# RC_Receiver.net
KiCad netlist of a schematic drawn in EAGLE
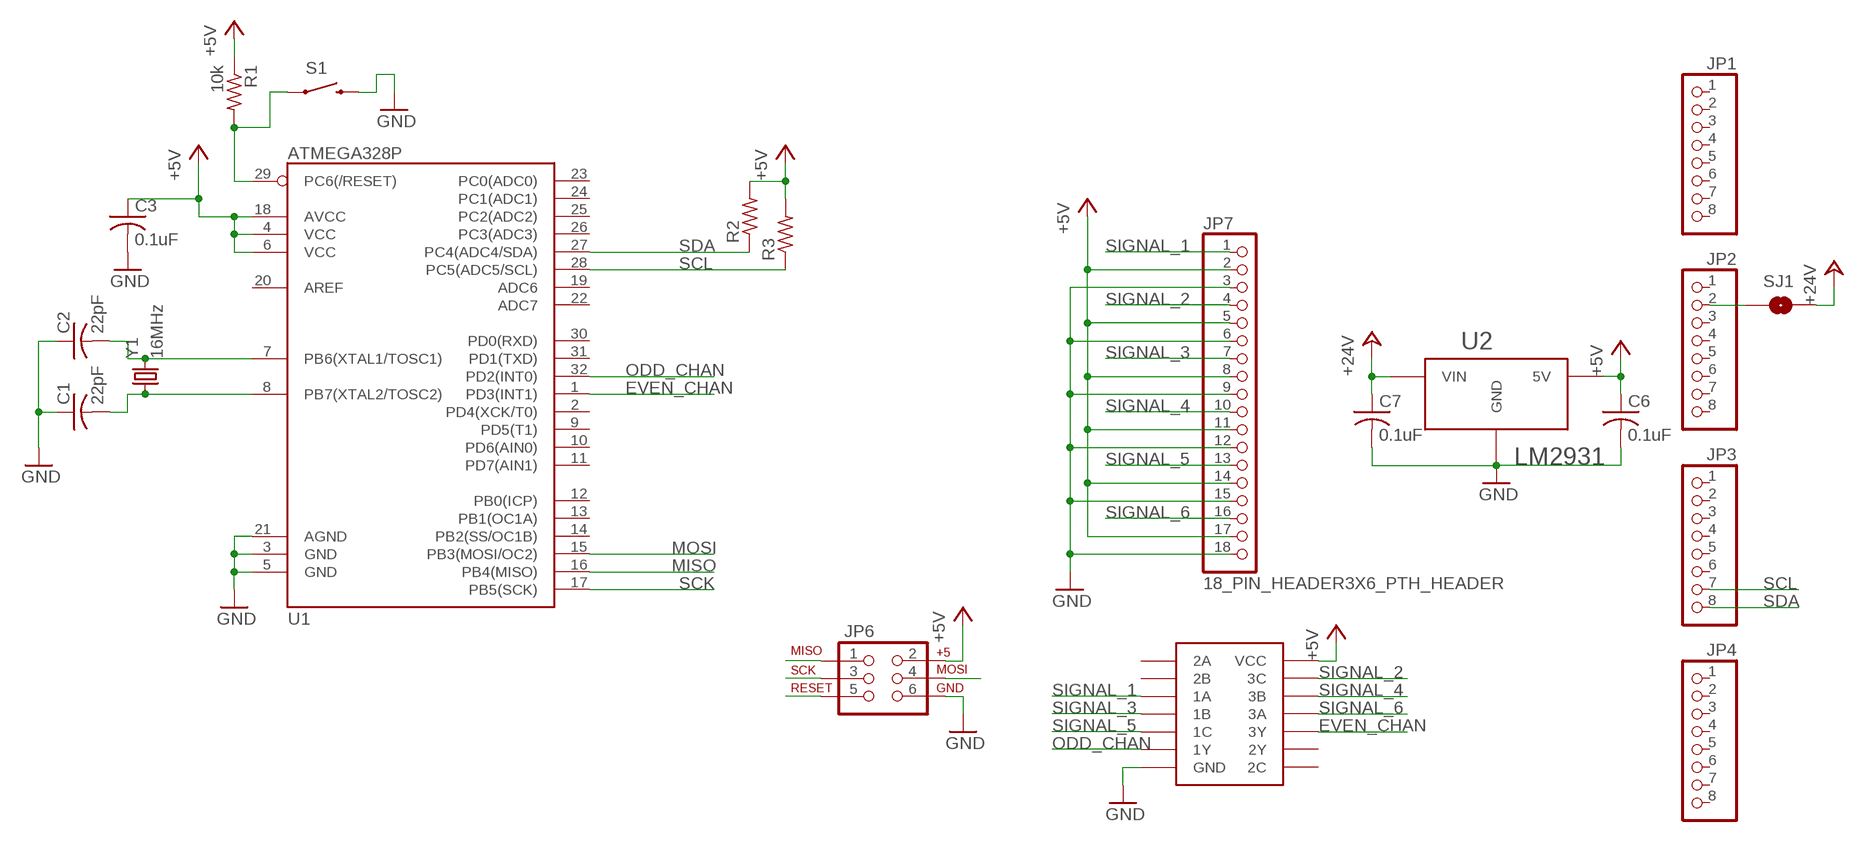
[diagram p0: schematic, sheet 1]

(export (version "E")
  (design (tool "Eeschema 10.0.6"))
  (components
    (comp (ref "C1")
      (value "22pF")
      (footprint "eagle-import:C0603")
      (libsource (lib "eagle-import") (part "C-USC0603"))
    )
    (comp (ref "C2")
      (value "22pF")
      (footprint "eagle-import:C0603")
      (libsource (lib "eagle-import") (part "C-USC0603"))
    )
    (comp (ref "C3")
      (value "0.1uF")
      (footprint "eagle-import:C0603")
      (libsource (lib "eagle-import") (part "C-USC0603"))
    )
    (comp (ref "C6")
      (value "0.1uF")
      (footprint "eagle-import:C0603")
      (libsource (lib "eagle-import") (part "C-USC0603"))
    )
    (comp (ref "C7")
      (value "0.1uF")
      (footprint "eagle-import:C0603")
      (libsource (lib "eagle-import") (part "C-USC0603"))
    )
    (comp (ref "JP1")
      (value "PINHD-1X81X08_NO_SILK")
      (footprint "eagle-import:1X08_NO_SS")
      (libsource (lib "eagle-import") (part "PINHD-1X81X08_NO_SILK"))
    )
    (comp (ref "JP2")
      (value "PINHD-1X81X08_NO_SILK")
      (footprint "eagle-import:1X08_NO_SS")
      (libsource (lib "eagle-import") (part "PINHD-1X81X08_NO_SILK"))
    )
    (comp (ref "JP3")
      (value "PINHD-1X81X08_NO_SILK")
      (footprint "eagle-import:1X08_NO_SS")
      (libsource (lib "eagle-import") (part "PINHD-1X81X08_NO_SILK"))
    )
    (comp (ref "JP4")
      (value "PINHD-1X81X08_NO_SILK")
      (footprint "eagle-import:1X08_NO_SS")
      (libsource (lib "eagle-import") (part "PINHD-1X81X08_NO_SILK"))
    )
    (comp (ref "JP6")
      (value "AVR_SPI_PRG_62X3_LOCK")
      (footprint "eagle-import:2X3_LOCK")
      (libsource (lib "eagle-import") (part "AVR_SPI_PRG_62X3_LOCK"))
    )
    (comp (ref "JP7")
      (value "18_PIN_HEADER3X6_PTH_HEADER")
      (footprint "eagle-import:3X6_PTH_HEADER")
      (libsource (lib "eagle-import") (part "18_PIN_HEADER3X6_PTH_HEADER"))
    )
    (comp (ref "R1")
      (value "10k")
      (footprint "eagle-import:R0603")
      (libsource (lib "eagle-import") (part "R-US_R0603"))
    )
    (comp (ref "R2")
      (value "R-US_R0603")
      (footprint "eagle-import:R0603")
      (libsource (lib "eagle-import") (part "R-US_R0603"))
    )
    (comp (ref "R3")
      (value "R-US_R0603")
      (footprint "eagle-import:R0603")
      (libsource (lib "eagle-import") (part "R-US_R0603"))
    )
    (comp (ref "S1")
      (value "SWITCH-MOMENTARY-2SMD")
      (footprint "eagle-import:TACTILE_SWITCH_SMD")
      (libsource (lib "eagle-import") (part "SWITCH-MOMENTARY-2SMD"))
    )
    (comp (ref "SJ1")
      (value "SOLDERJUMPERNC")
      (footprint "eagle-import:SJ_2S")
      (libsource (lib "eagle-import") (part "SOLDERJUMPERNC"))
    )
    (comp (ref "U$1")
      (value "C74HC407514-SOIC")
      (footprint "eagle-import:14-SOIC")
      (fields (field (name "PART#") "296-14534-1-ND"))
      (libsource (lib "eagle-import") (part "C74HC407514-SOIC"))
    )
    (comp (ref "U1")
      (value "ATMEGA328P")
      (footprint "eagle-import:TQFP32-08")
      (libsource (lib "eagle-import") (part "ATMEGA328_SMT"))
    )
    (comp (ref "U2")
      (value "LM2931")
      (footprint "eagle-import:TO263")
      (fields (field (name "PART#") "lm2931"))
      (libsource (lib "eagle-import") (part "LM2931"))
    )
    (comp (ref "Y1")
      (value "16MHz")
      (footprint "eagle-import:CRYSTAL-SMD-5X3")
      (fields (field (name "PART#") "535-10226-1-ND"))
      (libsource (lib "eagle-import") (part "CRYSTAL5X3"))
    )
  )
  (nets
    (net (code "1") (name "+5V") (class "Default")
      (node (ref "C3") (pin "1") (pinfunction "1_1") (pintype "passive"))
      (node (ref "C6") (pin "1") (pinfunction "1_1") (pintype "passive"))
      (node (ref "JP6") (pin "2") (pinfunction "2_2") (pintype "passive"))
      (node (ref "JP7") (pin "11") (pinfunction "11_11") (pintype "passive"))
      (node (ref "JP7") (pin "14") (pinfunction "14_14") (pintype "passive"))
      (node (ref "JP7") (pin "17") (pinfunction "17_17") (pintype "passive"))
      (node (ref "JP7") (pin "2") (pinfunction "2_2") (pintype "passive"))
      (node (ref "JP7") (pin "5") (pinfunction "5_5") (pintype "passive"))
      (node (ref "JP7") (pin "8") (pinfunction "8_8") (pintype "passive"))
      (node (ref "R1") (pin "1") (pinfunction "1_1") (pintype "passive"))
      (node (ref "R2") (pin "2") (pinfunction "2_2") (pintype "passive"))
      (node (ref "R3") (pin "2") (pinfunction "2_2") (pintype "passive"))
      (node (ref "U$1") (pin "P$14") (pinfunction "VCC_P$14") (pintype "power_in"))
      (node (ref "U1") (pin "18") (pinfunction "AVCC_18") (pintype "bidirectional"))
      (node (ref "U1") (pin "4") (pinfunction "VCC_4") (pintype "bidirectional"))
      (node (ref "U1") (pin "6") (pinfunction "VCC_6") (pintype "bidirectional"))
      (node (ref "U2") (pin "P$3") (pinfunction "5V_P$3") (pintype "bidirectional"))
    )
    (net (code "2") (name "+24V") (class "Default")
      (node (ref "C7") (pin "1") (pinfunction "1_1") (pintype "passive"))
      (node (ref "SJ1") (pin "2") (pinfunction "2_2") (pintype "passive"))
      (node (ref "U2") (pin "P$2") (pinfunction "VIN_P$2") (pintype "bidirectional"))
    )
    (net (code "3") (name "/EVEN_CHAN") (class "Default")
      (node (ref "U$1") (pin "P$12") (pinfunction "3Y_P$12") (pintype "bidirectional"))
      (node (ref "U1") (pin "1") (pinfunction "PD3(INT1)_1") (pintype "bidirectional"))
    )
    (net (code "4") (name "/MISO") (class "Default")
      (node (ref "JP6") (pin "1") (pinfunction "1_1") (pintype "passive"))
      (node (ref "U1") (pin "16") (pinfunction "PB4(MISO)_16") (pintype "bidirectional"))
    )
    (net (code "5") (name "/MOSI") (class "Default")
      (node (ref "JP6") (pin "4") (pinfunction "4_4") (pintype "passive"))
      (node (ref "U1") (pin "15") (pinfunction "PB3(MOSI/OC2)_15") (pintype "bidirectional"))
    )
    (net (code "6") (name "/ODD_CHAN") (class "Default")
      (node (ref "U$1") (pin "P$4") (pinfunction "1Y_P$4") (pintype "bidirectional"))
      (node (ref "U1") (pin "32") (pinfunction "PD2(INT0)_32") (pintype "bidirectional"))
    )
    (net (code "7") (name "/RESET") (class "Default")
      (node (ref "JP6") (pin "5") (pinfunction "5_5") (pintype "passive"))
      (node (ref "R1") (pin "2") (pinfunction "2_2") (pintype "passive"))
      (node (ref "S1") (pin "1") (pinfunction "1_1") (pintype "passive"))
      (node (ref "U1") (pin "29") (pinfunction "PC6(/RESET)_29") (pintype "bidirectional"))
    )
    (net (code "8") (name "/SCK") (class "Default")
      (node (ref "JP6") (pin "3") (pinfunction "3_3") (pintype "passive"))
      (node (ref "U1") (pin "17") (pinfunction "PB5(SCK)_17") (pintype "bidirectional"))
    )
    (net (code "9") (name "/SCL") (class "Default")
      (node (ref "JP3") (pin "7") (pinfunction "7_7") (pintype "passive"))
      (node (ref "R3") (pin "1") (pinfunction "1_1") (pintype "passive"))
      (node (ref "U1") (pin "28") (pinfunction "PC5(ADC5/SCL)_28") (pintype "bidirectional"))
    )
    (net (code "10") (name "/SDA") (class "Default")
      (node (ref "JP3") (pin "8") (pinfunction "8_8") (pintype "passive"))
      (node (ref "R2") (pin "1") (pinfunction "1_1") (pintype "passive"))
      (node (ref "U1") (pin "27") (pinfunction "PC4(ADC4/SDA)_27") (pintype "bidirectional"))
    )
    (net (code "11") (name "/SIGNAL_1") (class "Default")
      (node (ref "JP7") (pin "1") (pinfunction "1_1") (pintype "passive"))
      (node (ref "U$1") (pin "P$1") (pinfunction "1A_P$1") (pintype "bidirectional"))
    )
    (net (code "12") (name "/SIGNAL_2") (class "Default")
      (node (ref "JP7") (pin "4") (pinfunction "4_4") (pintype "passive"))
      (node (ref "U$1") (pin "P$11") (pinfunction "3C_P$11") (pintype "bidirectional"))
    )
    (net (code "13") (name "/SIGNAL_3") (class "Default")
      (node (ref "JP7") (pin "7") (pinfunction "7_7") (pintype "passive"))
      (node (ref "U$1") (pin "P$2") (pinfunction "1B_P$2") (pintype "bidirectional"))
    )
    (net (code "14") (name "/SIGNAL_4") (class "Default")
      (node (ref "JP7") (pin "10") (pinfunction "10_10") (pintype "passive"))
      (node (ref "U$1") (pin "P$10") (pinfunction "3B_P$10") (pintype "bidirectional"))
    )
    (net (code "15") (name "/SIGNAL_5") (class "Default")
      (node (ref "JP7") (pin "13") (pinfunction "13_13") (pintype "passive"))
      (node (ref "U$1") (pin "P$3") (pinfunction "1C_P$3") (pintype "bidirectional"))
    )
    (net (code "16") (name "/SIGNAL_6") (class "Default")
      (node (ref "JP7") (pin "16") (pinfunction "16_16") (pintype "passive"))
      (node (ref "U$1") (pin "P$9") (pinfunction "3A_P$9") (pintype "bidirectional"))
    )
    (net (code "17") (name "GND") (class "Default")
      (node (ref "C1") (pin "1") (pinfunction "1_1") (pintype "passive"))
      (node (ref "C2") (pin "1") (pinfunction "1_1") (pintype "passive"))
      (node (ref "C3") (pin "2") (pinfunction "2_2") (pintype "passive"))
      (node (ref "C6") (pin "2") (pinfunction "2_2") (pintype "passive"))
      (node (ref "C7") (pin "2") (pinfunction "2_2") (pintype "passive"))
      (node (ref "JP6") (pin "6") (pinfunction "6_6") (pintype "passive"))
      (node (ref "JP7") (pin "12") (pinfunction "12_12") (pintype "passive"))
      (node (ref "JP7") (pin "15") (pinfunction "15_15") (pintype "passive"))
      (node (ref "JP7") (pin "18") (pinfunction "18_18") (pintype "passive"))
      (node (ref "JP7") (pin "3") (pinfunction "3_3") (pintype "passive"))
      (node (ref "JP7") (pin "6") (pinfunction "6_6") (pintype "passive"))
      (node (ref "JP7") (pin "9") (pinfunction "9_9") (pintype "passive"))
      (node (ref "S1") (pin "3") (pinfunction "2_3") (pintype "passive"))
      (node (ref "U$1") (pin "P$13") (pinfunction "GND_P$13") (pintype "power_in"))
      (node (ref "U1") (pin "21") (pinfunction "AGND_21") (pintype "bidirectional"))
      (node (ref "U1") (pin "3") (pinfunction "GND_3") (pintype "bidirectional"))
      (node (ref "U1") (pin "5") (pinfunction "GND_5") (pintype "bidirectional"))
      (node (ref "U2") (pin "P$1") (pinfunction "GND_P$1") (pintype "bidirectional"))
    )
    (net (code "18") (name "Net-(JP2-Pad2)") (class "Default")
      (node (ref "JP2") (pin "2") (pinfunction "2_2") (pintype "passive"))
      (node (ref "SJ1") (pin "1") (pinfunction "1_1") (pintype "passive"))
    )
    (net (code "19") (name "Net-(U1-PB6(XTAL1{slash}TOSC1))") (class "Default")
      (node (ref "C2") (pin "2") (pinfunction "2_2") (pintype "passive"))
      (node (ref "U1") (pin "7") (pinfunction "PB6(XTAL1/TOSC1)_7") (pintype "bidirectional"))
      (node (ref "Y1") (pin "3") (pinfunction "2_3") (pintype "passive"))
    )
    (net (code "20") (name "Net-(U1-PB7(XTAL2{slash}TOSC2))") (class "Default")
      (node (ref "C1") (pin "2") (pinfunction "2_2") (pintype "passive"))
      (node (ref "U1") (pin "8") (pinfunction "PB7(XTAL2/TOSC2)_8") (pintype "bidirectional"))
      (node (ref "Y1") (pin "1") (pinfunction "1_1") (pintype "passive"))
    )
    (net (code "21") (name "unconnected-(JP1-Pad1)") (class "Default")
      (node (ref "JP1") (pin "1") (pinfunction "1_1") (pintype "passive"))
    )
    (net (code "22") (name "unconnected-(JP1-Pad2)") (class "Default")
      (node (ref "JP1") (pin "2") (pinfunction "2_2") (pintype "passive"))
    )
    (net (code "23") (name "unconnected-(JP1-Pad3)") (class "Default")
      (node (ref "JP1") (pin "3") (pinfunction "3_3") (pintype "passive"))
    )
    (net (code "24") (name "unconnected-(JP1-Pad4)") (class "Default")
      (node (ref "JP1") (pin "4") (pinfunction "4_4") (pintype "passive"))
    )
    (net (code "25") (name "unconnected-(JP1-Pad5)") (class "Default")
      (node (ref "JP1") (pin "5") (pinfunction "5_5") (pintype "passive"))
    )
    (net (code "26") (name "unconnected-(JP1-Pad6)") (class "Default")
      (node (ref "JP1") (pin "6") (pinfunction "6_6") (pintype "passive"))
    )
    (net (code "27") (name "unconnected-(JP1-Pad7)") (class "Default")
      (node (ref "JP1") (pin "7") (pinfunction "7_7") (pintype "passive"))
    )
    (net (code "28") (name "unconnected-(JP1-Pad8)") (class "Default")
      (node (ref "JP1") (pin "8") (pinfunction "8_8") (pintype "passive"))
    )
    (net (code "29") (name "unconnected-(JP2-Pad1)") (class "Default")
      (node (ref "JP2") (pin "1") (pinfunction "1_1") (pintype "passive"))
    )
    (net (code "30") (name "unconnected-(JP2-Pad3)") (class "Default")
      (node (ref "JP2") (pin "3") (pinfunction "3_3") (pintype "passive"))
    )
    (net (code "31") (name "unconnected-(JP2-Pad4)") (class "Default")
      (node (ref "JP2") (pin "4") (pinfunction "4_4") (pintype "passive"))
    )
    (net (code "32") (name "unconnected-(JP2-Pad5)") (class "Default")
      (node (ref "JP2") (pin "5") (pinfunction "5_5") (pintype "passive"))
    )
    (net (code "33") (name "unconnected-(JP2-Pad6)") (class "Default")
      (node (ref "JP2") (pin "6") (pinfunction "6_6") (pintype "passive"))
    )
    (net (code "34") (name "unconnected-(JP2-Pad7)") (class "Default")
      (node (ref "JP2") (pin "7") (pinfunction "7_7") (pintype "passive"))
    )
    (net (code "35") (name "unconnected-(JP2-Pad8)") (class "Default")
      (node (ref "JP2") (pin "8") (pinfunction "8_8") (pintype "passive"))
    )
    (net (code "36") (name "unconnected-(JP3-Pad1)") (class "Default")
      (node (ref "JP3") (pin "1") (pinfunction "1_1") (pintype "passive"))
    )
    (net (code "37") (name "unconnected-(JP3-Pad2)") (class "Default")
      (node (ref "JP3") (pin "2") (pinfunction "2_2") (pintype "passive"))
    )
    (net (code "38") (name "unconnected-(JP3-Pad3)") (class "Default")
      (node (ref "JP3") (pin "3") (pinfunction "3_3") (pintype "passive"))
    )
    (net (code "39") (name "unconnected-(JP3-Pad4)") (class "Default")
      (node (ref "JP3") (pin "4") (pinfunction "4_4") (pintype "passive"))
    )
    (net (code "40") (name "unconnected-(JP3-Pad5)") (class "Default")
      (node (ref "JP3") (pin "5") (pinfunction "5_5") (pintype "passive"))
    )
    (net (code "41") (name "unconnected-(JP3-Pad6)") (class "Default")
      (node (ref "JP3") (pin "6") (pinfunction "6_6") (pintype "passive"))
    )
    (net (code "42") (name "unconnected-(JP4-Pad1)") (class "Default")
      (node (ref "JP4") (pin "1") (pinfunction "1_1") (pintype "passive"))
    )
    (net (code "43") (name "unconnected-(JP4-Pad2)") (class "Default")
      (node (ref "JP4") (pin "2") (pinfunction "2_2") (pintype "passive"))
    )
    (net (code "44") (name "unconnected-(JP4-Pad3)") (class "Default")
      (node (ref "JP4") (pin "3") (pinfunction "3_3") (pintype "passive"))
    )
    (net (code "45") (name "unconnected-(JP4-Pad4)") (class "Default")
      (node (ref "JP4") (pin "4") (pinfunction "4_4") (pintype "passive"))
    )
    (net (code "46") (name "unconnected-(JP4-Pad5)") (class "Default")
      (node (ref "JP4") (pin "5") (pinfunction "5_5") (pintype "passive"))
    )
    (net (code "47") (name "unconnected-(JP4-Pad6)") (class "Default")
      (node (ref "JP4") (pin "6") (pinfunction "6_6") (pintype "passive"))
    )
    (net (code "48") (name "unconnected-(JP4-Pad7)") (class "Default")
      (node (ref "JP4") (pin "7") (pinfunction "7_7") (pintype "passive"))
    )
    (net (code "49") (name "unconnected-(JP4-Pad8)") (class "Default")
      (node (ref "JP4") (pin "8") (pinfunction "8_8") (pintype "passive"))
    )
    (net (code "50") (name "unconnected-(U$1-2A-PadP$5)") (class "Default")
      (node (ref "U$1") (pin "P$5") (pinfunction "2A_P$5") (pintype "bidirectional"))
    )
    (net (code "51") (name "unconnected-(U$1-2B-PadP$6)") (class "Default")
      (node (ref "U$1") (pin "P$6") (pinfunction "2B_P$6") (pintype "bidirectional"))
    )
    (net (code "52") (name "unconnected-(U$1-2C-PadP$7)") (class "Default")
      (node (ref "U$1") (pin "P$7") (pinfunction "2C_P$7") (pintype "bidirectional"))
    )
    (net (code "53") (name "unconnected-(U$1-2Y-PadP$8)") (class "Default")
      (node (ref "U$1") (pin "P$8") (pinfunction "2Y_P$8") (pintype "bidirectional"))
    )
    (net (code "54") (name "unconnected-(U1-ADC6-Pad19)") (class "Default")
      (node (ref "U1") (pin "19") (pinfunction "ADC6_19") (pintype "bidirectional"))
    )
    (net (code "55") (name "unconnected-(U1-ADC7-Pad22)") (class "Default")
      (node (ref "U1") (pin "22") (pinfunction "ADC7_22") (pintype "bidirectional"))
    )
    (net (code "56") (name "unconnected-(U1-AREF-Pad20)") (class "Default")
      (node (ref "U1") (pin "20") (pinfunction "AREF_20") (pintype "bidirectional"))
    )
    (net (code "57") (name "unconnected-(U1-PB0(ICP)-Pad12)") (class "Default")
      (node (ref "U1") (pin "12") (pinfunction "PB0(ICP)_12") (pintype "bidirectional"))
    )
    (net (code "58") (name "unconnected-(U1-PB1(OC1A)-Pad13)") (class "Default")
      (node (ref "U1") (pin "13") (pinfunction "PB1(OC1A)_13") (pintype "bidirectional"))
    )
    (net (code "59") (name "unconnected-(U1-PB2(SS{slash}OC1B)-Pad14)") (class "Default")
      (node (ref "U1") (pin "14") (pinfunction "PB2(SS/OC1B)_14") (pintype "bidirectional"))
    )
    (net (code "60") (name "unconnected-(U1-PC0(ADC0)-Pad23)") (class "Default")
      (node (ref "U1") (pin "23") (pinfunction "PC0(ADC0)_23") (pintype "bidirectional"))
    )
    (net (code "61") (name "unconnected-(U1-PC1(ADC1)-Pad24)") (class "Default")
      (node (ref "U1") (pin "24") (pinfunction "PC1(ADC1)_24") (pintype "bidirectional"))
    )
    (net (code "62") (name "unconnected-(U1-PC2(ADC2)-Pad25)") (class "Default")
      (node (ref "U1") (pin "25") (pinfunction "PC2(ADC2)_25") (pintype "bidirectional"))
    )
    (net (code "63") (name "unconnected-(U1-PC3(ADC3)-Pad26)") (class "Default")
      (node (ref "U1") (pin "26") (pinfunction "PC3(ADC3)_26") (pintype "bidirectional"))
    )
    (net (code "64") (name "unconnected-(U1-PD0(RXD)-Pad30)") (class "Default")
      (node (ref "U1") (pin "30") (pinfunction "PD0(RXD)_30") (pintype "bidirectional"))
    )
    (net (code "65") (name "unconnected-(U1-PD1(TXD)-Pad31)") (class "Default")
      (node (ref "U1") (pin "31") (pinfunction "PD1(TXD)_31") (pintype "bidirectional"))
    )
    (net (code "66") (name "unconnected-(U1-PD4(XCK{slash}T0)-Pad2)") (class "Default")
      (node (ref "U1") (pin "2") (pinfunction "PD4(XCK/T0)_2") (pintype "bidirectional"))
    )
    (net (code "67") (name "unconnected-(U1-PD5(T1)-Pad9)") (class "Default")
      (node (ref "U1") (pin "9") (pinfunction "PD5(T1)_9") (pintype "bidirectional"))
    )
    (net (code "68") (name "unconnected-(U1-PD6(AIN0)-Pad10)") (class "Default")
      (node (ref "U1") (pin "10") (pinfunction "PD6(AIN0)_10") (pintype "bidirectional"))
    )
    (net (code "69") (name "unconnected-(U1-PD7(AIN1)-Pad11)") (class "Default")
      (node (ref "U1") (pin "11") (pinfunction "PD7(AIN1)_11") (pintype "bidirectional"))
    )
  )
)
